# Bell003.net
KiCad netlist of a schematic drawn in EAGLE
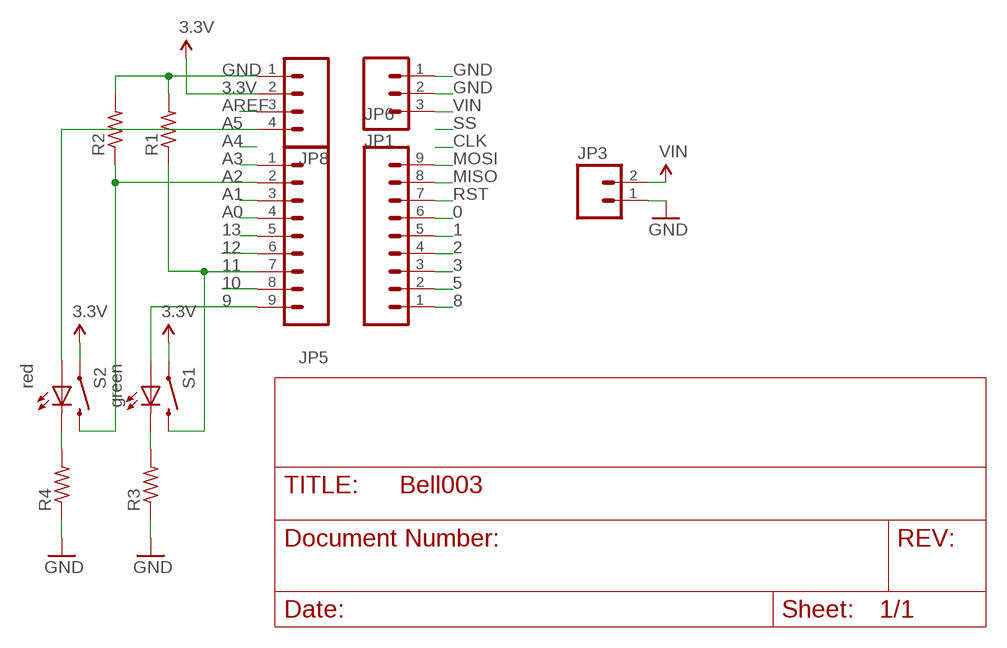
[diagram p0: schematic, sheet 1]

(export (version "E")
  (design (tool "Eeschema 10.0.6"))
  (components
    (comp (ref "JP1")
      (value "M03PTH")
      (footprint "eagle-import:1X03")
      (libsource (lib "eagle-import") (part "M03PTH"))
    )
    (comp (ref "JP3")
      (value "M02-JST-2-PTH-NO_SILK")
      (footprint "eagle-import:JST-2-PTH-NS")
      (libsource (lib "eagle-import") (part "M02-JST-2-PTH-NO_SILK"))
    )
    (comp (ref "JP5")
      (value "M09")
      (footprint "eagle-import:1X09")
      (libsource (lib "eagle-import") (part "M09"))
    )
    (comp (ref "JP6")
      (value "M09")
      (footprint "eagle-import:1X09")
      (libsource (lib "eagle-import") (part "M09"))
    )
    (comp (ref "JP8")
      (value "M04PTH")
      (footprint "eagle-import:1X04")
      (libsource (lib "eagle-import") (part "M04PTH"))
    )
    (comp (ref "R1")
      (value "RES-US1206FAB")
      (footprint "eagle-import:R1206FAB")
      (libsource (lib "eagle-import") (part "RES-US1206FAB"))
    )
    (comp (ref "R2")
      (value "RES-US1206FAB")
      (footprint "eagle-import:R1206FAB")
      (libsource (lib "eagle-import") (part "RES-US1206FAB"))
    )
    (comp (ref "R3")
      (value "RES-US1206FAB")
      (footprint "eagle-import:R1206FAB")
      (libsource (lib "eagle-import") (part "RES-US1206FAB"))
    )
    (comp (ref "R4")
      (value "RES-US1206FAB")
      (footprint "eagle-import:R1206FAB")
      (libsource (lib "eagle-import") (part "RES-US1206FAB"))
    )
    (comp (ref "S1")
      (value "green")
      (footprint "eagle-import:TACTILE-PTH-LED-12MM")
      (libsource (lib "eagle-import") (part "SWITCH-MOMENTARY-LEDPTH"))
    )
    (comp (ref "S2")
      (value "red")
      (footprint "eagle-import:TACTILE-PTH-LED-12MM")
      (libsource (lib "eagle-import") (part "SWITCH-MOMENTARY-LEDPTH"))
    )
  )
  (nets
    (net (code "1") (name "/0") (class "Default")
      (node (ref "JP6") (pin "6") (pinfunction "6_6") (pintype "passive"))
    )
    (net (code "2") (name "/1") (class "Default")
      (node (ref "JP6") (pin "5") (pinfunction "5_5") (pintype "passive"))
    )
    (net (code "3") (name "/2") (class "Default")
      (node (ref "JP6") (pin "4") (pinfunction "4_4") (pintype "passive"))
    )
    (net (code "4") (name "/3") (class "Default")
      (node (ref "JP6") (pin "3") (pinfunction "3_3") (pintype "passive"))
    )
    (net (code "5") (name "/5") (class "Default")
      (node (ref "JP6") (pin "2") (pinfunction "2_2") (pintype "passive"))
    )
    (net (code "6") (name "/8") (class "Default")
      (node (ref "JP6") (pin "1") (pinfunction "1_1") (pintype "passive"))
    )
    (net (code "7") (name "/9") (class "Default")
      (node (ref "JP5") (pin "9") (pinfunction "9_9") (pintype "passive"))
      (node (ref "S1") (pin "A") (pinfunction "A_A") (pintype "passive"))
    )
    (net (code "8") (name "/10") (class "Default")
      (node (ref "JP5") (pin "8") (pinfunction "8_8") (pintype "passive"))
    )
    (net (code "9") (name "/11") (class "Default")
      (node (ref "JP5") (pin "7") (pinfunction "7_7") (pintype "passive"))
      (node (ref "R1") (pin "1") (pinfunction "1_1") (pintype "passive"))
      (node (ref "S1") (pin "2") (pinfunction "2_2") (pintype "passive"))
    )
    (net (code "10") (name "/12") (class "Default")
      (node (ref "JP5") (pin "6") (pinfunction "6_6") (pintype "passive"))
    )
    (net (code "11") (name "/13") (class "Default")
      (node (ref "JP5") (pin "5") (pinfunction "5_5") (pintype "passive"))
    )
    (net (code "12") (name "/A0") (class "Default")
      (node (ref "JP5") (pin "4") (pinfunction "4_4") (pintype "passive"))
    )
    (net (code "13") (name "/A1") (class "Default")
      (node (ref "JP5") (pin "3") (pinfunction "3_3") (pintype "passive"))
    )
    (net (code "14") (name "/A2") (class "Default")
      (node (ref "JP5") (pin "2") (pinfunction "2_2") (pintype "passive"))
      (node (ref "R2") (pin "1") (pinfunction "1_1") (pintype "passive"))
      (node (ref "S2") (pin "2") (pinfunction "2_2") (pintype "passive"))
    )
    (net (code "15") (name "/A3") (class "Default")
      (node (ref "JP5") (pin "1") (pinfunction "1_1") (pintype "passive"))
    )
    (net (code "17") (name "/A5") (class "Default")
      (node (ref "JP8") (pin "4") (pinfunction "4_4") (pintype "passive"))
      (node (ref "S2") (pin "A") (pinfunction "A_A") (pintype "passive"))
    )
    (net (code "18") (name "/AREF") (class "Default")
      (node (ref "JP8") (pin "3") (pinfunction "3_3") (pintype "passive"))
    )
    (net (code "20") (name "/MISO") (class "Default")
      (node (ref "JP6") (pin "8") (pinfunction "8_8") (pintype "passive"))
    )
    (net (code "21") (name "/MOSI") (class "Default")
      (node (ref "JP6") (pin "9") (pinfunction "9_9") (pintype "passive"))
    )
    (net (code "22") (name "/RST") (class "Default")
      (node (ref "JP6") (pin "7") (pinfunction "7_7") (pintype "passive"))
    )
    (net (code "24") (name "3.3V") (class "Default")
      (node (ref "JP8") (pin "2") (pinfunction "2_2") (pintype "passive"))
      (node (ref "S1") (pin "4") (pinfunction "1_4") (pintype "passive"))
      (node (ref "S2") (pin "4") (pinfunction "1_4") (pintype "passive"))
    )
    (net (code "25") (name "GND") (class "Default")
      (node (ref "JP1") (pin "1") (pinfunction "1_1") (pintype "passive"))
      (node (ref "JP1") (pin "2") (pinfunction "2_2") (pintype "passive"))
      (node (ref "JP3") (pin "1") (pinfunction "1_1") (pintype "passive"))
      (node (ref "JP8") (pin "1") (pinfunction "1_1") (pintype "passive"))
      (node (ref "R1") (pin "2") (pinfunction "2_2") (pintype "passive"))
      (node (ref "R2") (pin "2") (pinfunction "2_2") (pintype "passive"))
      (node (ref "R3") (pin "1") (pinfunction "1_1") (pintype "passive"))
      (node (ref "R4") (pin "1") (pinfunction "1_1") (pintype "passive"))
    )
    (net (code "26") (name "Net-(R3-Pad2)") (class "Default")
      (node (ref "R3") (pin "2") (pinfunction "2_2") (pintype "passive"))
      (node (ref "S1") (pin "C") (pinfunction "C_C") (pintype "passive"))
    )
    (net (code "27") (name "Net-(R4-Pad2)") (class "Default")
      (node (ref "R4") (pin "2") (pinfunction "2_2") (pintype "passive"))
      (node (ref "S2") (pin "C") (pinfunction "C_C") (pintype "passive"))
    )
    (net (code "28") (name "VIN") (class "Default")
      (node (ref "JP1") (pin "3") (pinfunction "3_3") (pintype "passive"))
      (node (ref "JP3") (pin "2") (pinfunction "2_2") (pintype "passive"))
    )
  )
)
